# ESP32_Module.net
KiCad netlist of a schematic drawn in EAGLE
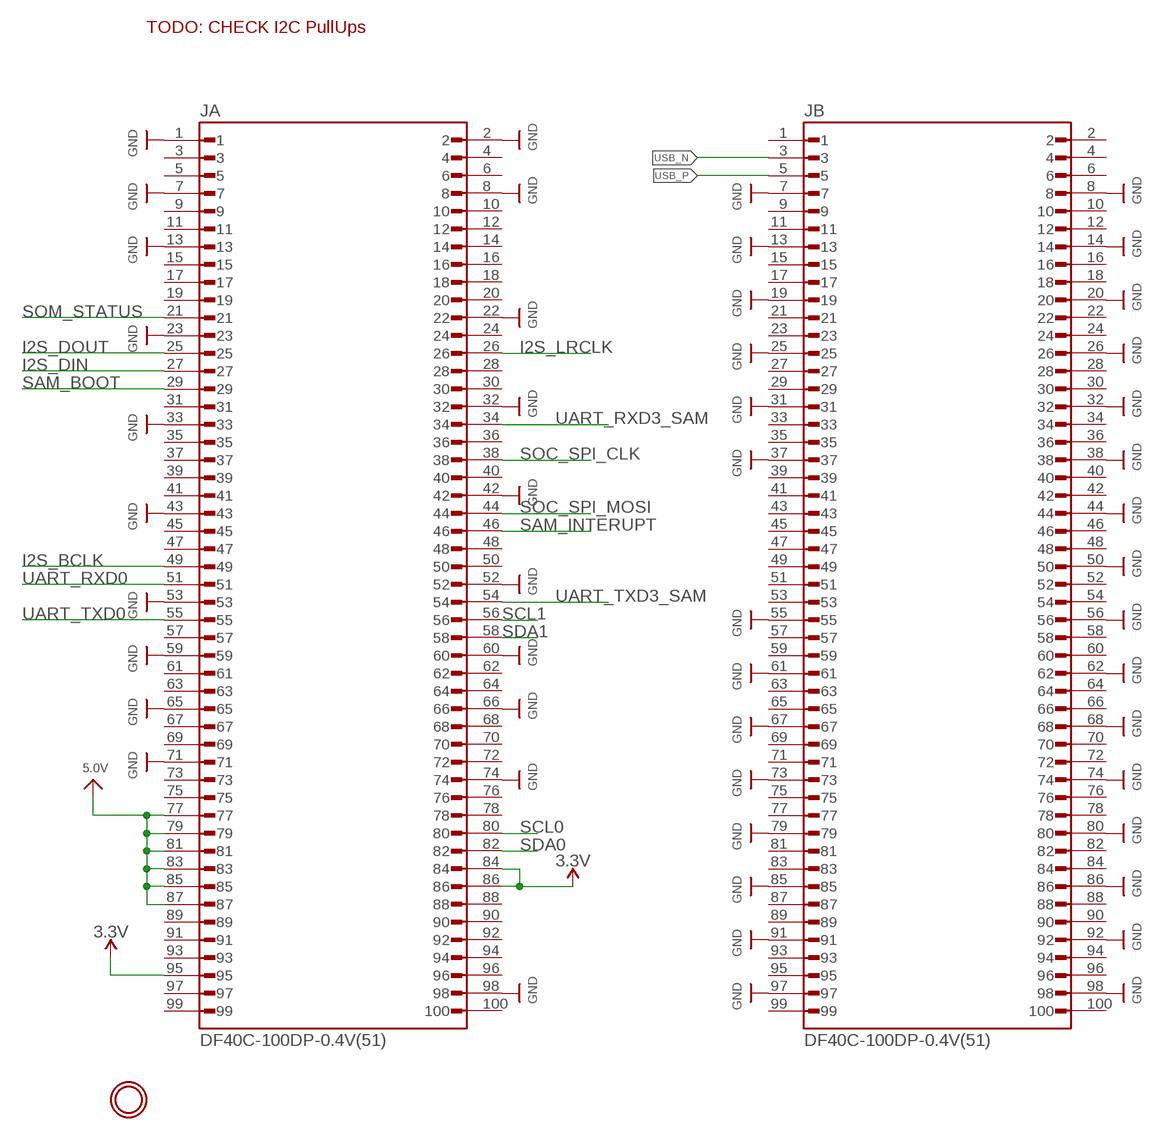
[diagram p0: schematic, sheet 1, part 1 of 3]
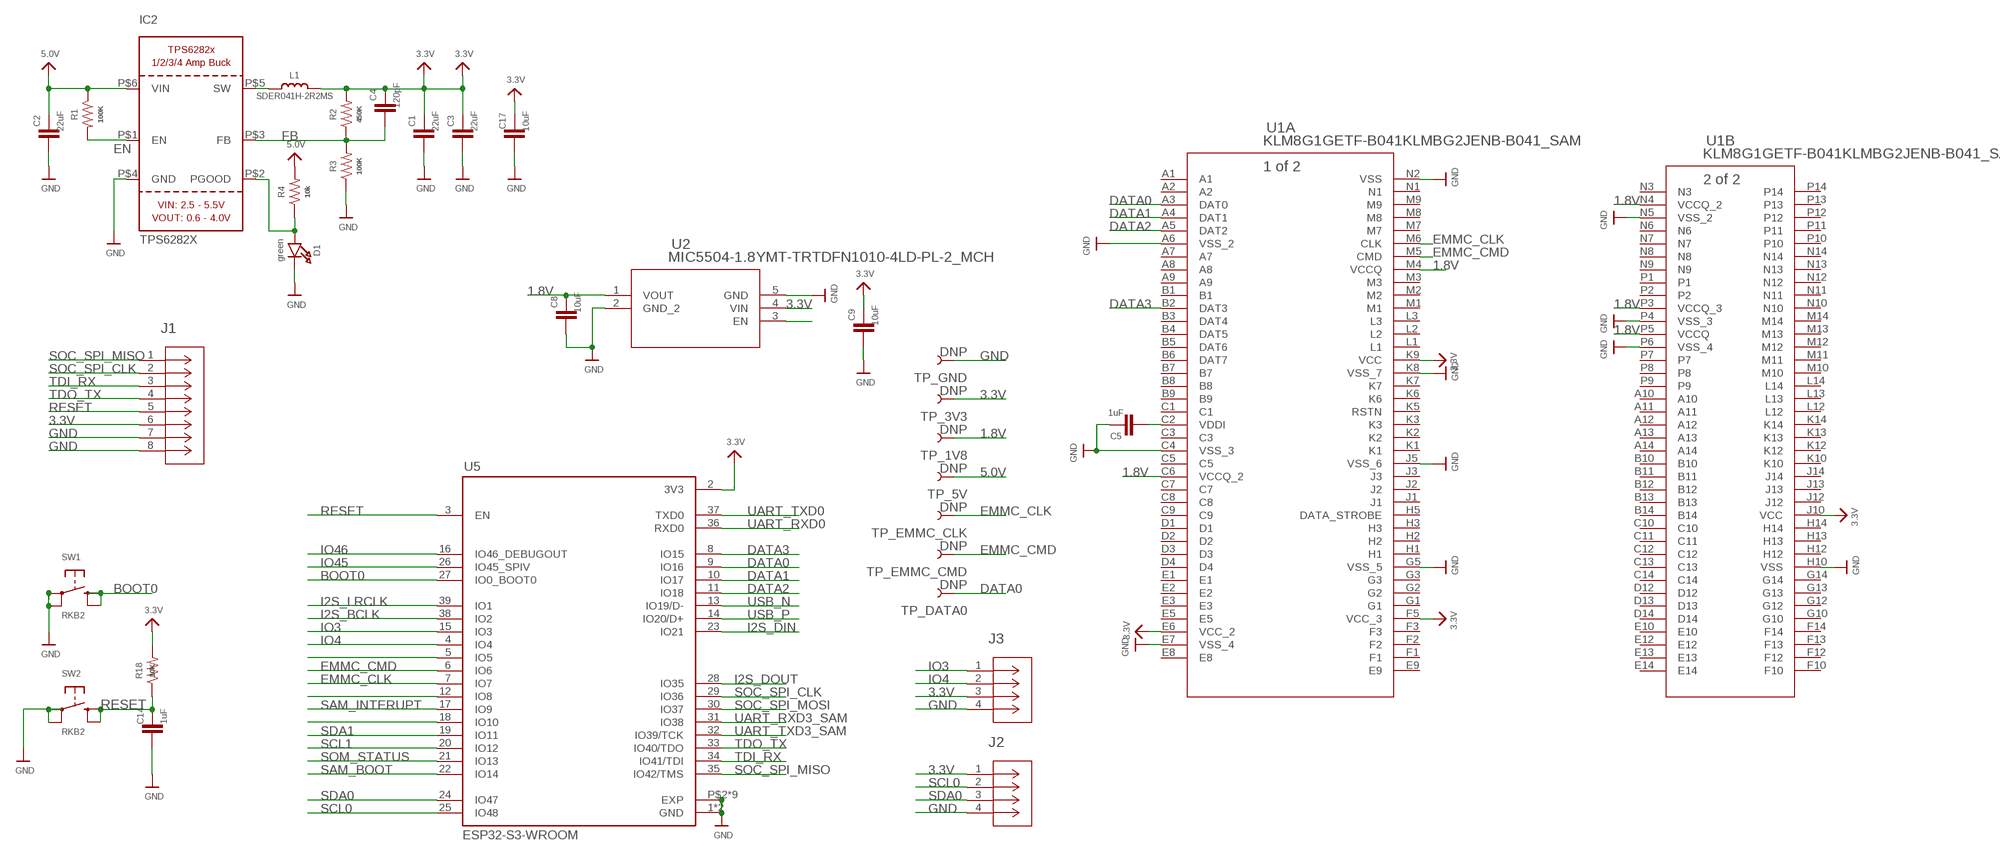
[diagram p1: schematic, sheet 1, part 2 of 3]
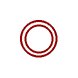
[diagram p2: schematic, sheet 1, part 3 of 3]

(export (version "E")
  (design (tool "Eeschema 10.0.6"))
  (components
    (comp (ref "C1")
      (value "22uF")
      (footprint "eagle-import:CAPC1005X60")
      (libsource (lib "eagle-import") (part "CCHIP-0402(1005-METRIC)_"))
    )
    (comp (ref "C2")
      (value "22uF")
      (footprint "eagle-import:CAPC1608X85")
      (libsource (lib "eagle-import") (part "CCHIP-0603(1608-METRIC)_"))
    )
    (comp (ref "C3")
      (value "22uF")
      (footprint "eagle-import:CAPC1005X60")
      (libsource (lib "eagle-import") (part "CCHIP-0402(1005-METRIC)_"))
    )
    (comp (ref "C4")
      (value "120pF")
      (footprint "eagle-import:CAPC1005X60")
      (libsource (lib "eagle-import") (part "CCHIP-0402(1005-METRIC)_"))
    )
    (comp (ref "C5")
      (value "1uF")
      (footprint "eagle-import:CAPC1005X60")
      (libsource (lib "eagle-import") (part "CCHIP-0402(1005-METRIC)_"))
    )
    (comp (ref "C8")
      (value "10uF")
      (footprint "eagle-import:CAPC1005X60")
      (libsource (lib "eagle-import") (part "CCHIP-0402(1005-METRIC)_"))
    )
    (comp (ref "C9")
      (value "10uF")
      (footprint "eagle-import:CAPC1005X60")
      (libsource (lib "eagle-import") (part "CCHIP-0402(1005-METRIC)_"))
    )
    (comp (ref "C14")
      (value "1uF")
      (footprint "eagle-import:CAPC1005X60")
      (libsource (lib "eagle-import") (part "CCHIP-0402(1005-METRIC)_"))
    )
    (comp (ref "C17")
      (value "10uF")
      (footprint "eagle-import:CAPC1005X60")
      (libsource (lib "eagle-import") (part "CCHIP-0402(1005-METRIC)_"))
    )
    (comp (ref "D1")
      (value "green")
      (footprint "eagle-import:CHIPLED_0603_NOOUTLINE")
      (libsource (lib "eagle-import") (part "LED0603_NOOUTLINE"))
    )
    (comp (ref "IC2")
      (value "TPS6282X")
      (footprint "eagle-import:VSON_6")
      (libsource (lib "eagle-import") (part "TPS6282X"))
    )
    (comp (ref "J1")
      (value "SM08B-SRSS-TB(LF)(SN)CONN_SM08B-SRSS-TB(LF)(SN)_JST")
      (footprint "eagle-import:CONN_SM08B-SRSS-TB(LF)(SN)_JST")
      (fields
        (field (name "MANUFACTURER_PART_NUMBER") "SM08B-SRSS-TB(LF)(SN)")
        (field (name "COPYRIGHT") "Copyright (C) 2024 Ultra Librarian. All rights reserved.")
      )
      (libsource (lib "eagle-import") (part "SM08B-SRSS-TB(LF)(SN)CONN_SM08B-SRSS-TB(LF)(SN)_JST"))
    )
    (comp (ref "J2")
      (value "SM04B-SRSS-TBCONN_SM04B-SRSS-TB_JST")
      (footprint "eagle-import:CONN_SM04B-SRSS-TB_JST")
      (fields
        (field (name "MANUFACTURER_PART_NUMBER") "SM04B-SRSS-TB")
        (field (name "COPYRIGHT") "Copyright (C) 2024 Ultra Librarian. All rights reserved.")
      )
      (libsource (lib "eagle-import") (part "SM04B-SRSS-TBCONN_SM04B-SRSS-TB_JST"))
    )
    (comp (ref "J3")
      (value "SM04B-SRSS-TBCONN_SM04B-SRSS-TB_JST")
      (footprint "eagle-import:CONN_SM04B-SRSS-TB_JST")
      (fields
        (field (name "MANUFACTURER_PART_NUMBER") "SM04B-SRSS-TB")
        (field (name "COPYRIGHT") "Copyright (C) 2024 Ultra Librarian. All rights reserved.")
      )
      (libsource (lib "eagle-import") (part "SM04B-SRSS-TBCONN_SM04B-SRSS-TB_JST"))
    )
    (comp (ref "JA")
      (value "DF40C-100DP-0.4V(51)")
      (footprint "eagle-import:HIROSE_DF40C-100DP-0.4V(51)")
      (fields (field (name "MANUFACTURER") "Hirose"))
      (libsource (lib "eagle-import") (part "DF40C-100DP-0.4V(51)"))
    )
    (comp (ref "JB")
      (value "DF40C-100DP-0.4V(51)")
      (footprint "eagle-import:HIROSE_DF40C-100DP-0.4V(51)")
      (fields (field (name "MANUFACTURER") "Hirose"))
      (libsource (lib "eagle-import") (part "DF40C-100DP-0.4V(51)"))
    )
    (comp (ref "L1")
      (value "SDER041H-2R2MS")
      (footprint "eagle-import:INDUCTOR_4X4MM_SRP0415")
      (libsource (lib "eagle-import") (part "INDUCTOR_SRP0415"))
    )
    (comp (ref "R1")
      (value "100K")
      (footprint "eagle-import:RESC1005X40")
      (libsource (lib "eagle-import") (part "R-USCHIP-0402(1005-METRIC)_"))
    )
    (comp (ref "R2")
      (value "450K")
      (footprint "eagle-import:RESC1005X40")
      (libsource (lib "eagle-import") (part "R-USCHIP-0402(1005-METRIC)_"))
    )
    (comp (ref "R3")
      (value "100K")
      (footprint "eagle-import:RESC1005X40")
      (libsource (lib "eagle-import") (part "R-USCHIP-0402(1005-METRIC)_"))
    )
    (comp (ref "R4")
      (value "10k")
      (footprint "eagle-import:RESC1005X40")
      (libsource (lib "eagle-import") (part "R-USCHIP-0402(1005-METRIC)_"))
    )
    (comp (ref "R18")
      (value "10K")
      (footprint "eagle-import:RESC1005X40")
      (libsource (lib "eagle-import") (part "R-USCHIP-0402(1005-METRIC)_"))
    )
    (comp (ref "SW1")
      (value "RKB2")
      (footprint "eagle-import:BTN_RKB2_4.6X2.8")
      (libsource (lib "eagle-import") (part "SWITCH_TACT_SMT_RKB2"))
    )
    (comp (ref "SW2")
      (value "RKB2")
      (footprint "eagle-import:BTN_RKB2_4.6X2.8")
      (libsource (lib "eagle-import") (part "SWITCH_TACT_SMT_RKB2"))
    )
    (comp (ref "TP_1V8")
      (value "DNP")
      (footprint "eagle-import:PAD.03X.03")
      (libsource (lib "eagle-import") (part "TEST-POINT3"))
    )
    (comp (ref "TP_3V3")
      (value "DNP")
      (footprint "eagle-import:PAD.03X.03")
      (libsource (lib "eagle-import") (part "TEST-POINT3"))
    )
    (comp (ref "TP_5V")
      (value "DNP")
      (footprint "eagle-import:PAD.03X.03")
      (libsource (lib "eagle-import") (part "TEST-POINT3"))
    )
    (comp (ref "TP_DATA0")
      (value "DNP")
      (footprint "eagle-import:PAD.03X.03")
      (libsource (lib "eagle-import") (part "TEST-POINT3"))
    )
    (comp (ref "TP_EMMC_CLK")
      (value "DNP")
      (footprint "eagle-import:PAD.03X.03")
      (libsource (lib "eagle-import") (part "TEST-POINT3"))
    )
    (comp (ref "TP_EMMC_CMD")
      (value "DNP")
      (footprint "eagle-import:PAD.03X.03")
      (libsource (lib "eagle-import") (part "TEST-POINT3"))
    )
    (comp (ref "TP_GND")
      (value "DNP")
      (footprint "eagle-import:PAD.03X.03")
      (libsource (lib "eagle-import") (part "TEST-POINT3"))
    )
    (comp (ref "U$2")
      (value "MOUNTINGHOLE2.5")
      (footprint "eagle-import:MOUNTINGHOLE_2.5_PLATED")
      (libsource (lib "eagle-import") (part "MOUNTINGHOLE2.5"))
    )
    (comp (ref "U$120")
      (value "MOUNTINGHOLE2.5")
      (footprint "eagle-import:MOUNTINGHOLE_2.5_PLATED")
      (libsource (lib "eagle-import") (part "MOUNTINGHOLE2.5"))
    )
    (comp (ref "U1")
      (value "KLM8G1GETF-B041KLMBG2JENB-B041_SAM")
      (footprint "eagle-import:KLMBG2JENB-B041_SAM")
      (fields
        (field (name "MANUFACTURER_PART_NUMBER") "KLM8G1GETF-B041")
        (field (name "COPYRIGHT") "Copyright (C) 2024 Ultra Librarian. All rights reserved.")
      )
      (libsource (lib "eagle-import") (part "KLM8G1GETF-B041KLMBG2JENB-B041_SAM"))
    )
    (comp (ref "U2")
      (value "MIC5504-1.8YMT-TRTDFN1010-4LD-PL-2_MCH")
      (footprint "eagle-import:TDFN1010-4LD-PL-2_MCH")
      (fields
        (field (name "MANUFACTURER_PART_NUMBER") "MIC5504-1.8YMT-TR")
        (field (name "COPYRIGHT") "Copyright (C) 2024 Ultra Librarian. All rights reserved.")
      )
      (libsource (lib "eagle-import") (part "MIC5504-1.8YMT-TRTDFN1010-4LD-PL-2_MCH"))
    )
    (comp (ref "U5")
      (value "ESP32-S3-WROOM")
      (footprint "eagle-import:S3-WROOM32")
      (libsource (lib "eagle-import") (part "ESP32-S3-WROOM"))
    )
  )
  (nets
    (net (code "1") (name "/1.8V") (class "Default")
      (node (ref "C8") (pin "1") (pinfunction "1_1") (pintype "passive"))
      (node (ref "TP_1V8") (pin "P$1") (pinfunction "1_P$1") (pintype "bidirectional"))
      (node (ref "U1") (pin "C6") (pinfunction "VCCQ_2_C6") (pintype "power_in"))
      (node (ref "U1") (pin "M4") (pinfunction "VCCQ_M4") (pintype "power_in"))
      (node (ref "U1") (pin "N4") (pinfunction "VCCQ_2_N4") (pintype "power_in"))
      (node (ref "U1") (pin "P3") (pinfunction "VCCQ_3_P3") (pintype "power_in"))
      (node (ref "U1") (pin "P5") (pinfunction "VCCQ_P5") (pintype "power_in"))
      (node (ref "U2") (pin "1") (pinfunction "VOUT_1") (pintype "output"))
    )
    (net (code "2") (name "/BOOT0") (class "Default")
      (node (ref "SW1") (pin "B") (pinfunction "S_B") (pintype "passive"))
      (node (ref "SW1") (pin "B'") (pinfunction "S1_B'") (pintype "passive"))
      (node (ref "U5") (pin "27") (pinfunction "IO0_BOOT0_27") (pintype "bidirectional"))
    )
    (net (code "3") (name "/DATA0") (class "Default")
      (node (ref "TP_DATA0") (pin "P$1") (pinfunction "1_P$1") (pintype "bidirectional"))
      (node (ref "U1") (pin "A3") (pinfunction "DAT0_A3") (pintype "bidirectional"))
      (node (ref "U5") (pin "9") (pinfunction "IO16_9") (pintype "bidirectional"))
    )
    (net (code "4") (name "/DATA1") (class "Default")
      (node (ref "U1") (pin "A4") (pinfunction "DAT1_A4") (pintype "bidirectional"))
      (node (ref "U5") (pin "10") (pinfunction "IO17_10") (pintype "bidirectional"))
    )
    (net (code "5") (name "/DATA2") (class "Default")
      (node (ref "U1") (pin "A5") (pinfunction "DAT2_A5") (pintype "bidirectional"))
      (node (ref "U5") (pin "11") (pinfunction "IO18_11") (pintype "bidirectional"))
    )
    (net (code "6") (name "/DATA3") (class "Default")
      (node (ref "U1") (pin "B2") (pinfunction "DAT3_B2") (pintype "bidirectional"))
      (node (ref "U5") (pin "8") (pinfunction "IO15_8") (pintype "bidirectional"))
    )
    (net (code "7") (name "/EMMC_CLK") (class "Default")
      (node (ref "TP_EMMC_CLK") (pin "P$1") (pinfunction "1_P$1") (pintype "bidirectional"))
      (node (ref "U1") (pin "M6") (pinfunction "CLK_M6") (pintype "passive"))
      (node (ref "U5") (pin "7") (pinfunction "IO7_7") (pintype "bidirectional"))
    )
    (net (code "8") (name "/EMMC_CMD") (class "Default")
      (node (ref "TP_EMMC_CMD") (pin "P$1") (pinfunction "1_P$1") (pintype "bidirectional"))
      (node (ref "U1") (pin "M5") (pinfunction "CMD_M5") (pintype "passive"))
      (node (ref "U5") (pin "6") (pinfunction "IO6_6") (pintype "bidirectional"))
    )
    (net (code "9") (name "/EN") (class "Default")
      (node (ref "IC2") (pin "P$1") (pinfunction "EN_P$1") (pintype "input"))
      (node (ref "R1") (pin "2") (pinfunction "2_2") (pintype "passive"))
    )
    (net (code "10") (name "/FB") (class "Default")
      (node (ref "C4") (pin "2") (pinfunction "2_2") (pintype "passive"))
      (node (ref "IC2") (pin "P$3") (pinfunction "FB_P$3") (pintype "input"))
      (node (ref "R2") (pin "1") (pinfunction "1_1") (pintype "passive"))
      (node (ref "R3") (pin "2") (pinfunction "2_2") (pintype "passive"))
    )
    (net (code "11") (name "/I2S_BCLK") (class "Default")
      (node (ref "JA") (pin "49") (pinfunction "49_49") (pintype "passive"))
      (node (ref "U5") (pin "38") (pinfunction "IO2_38") (pintype "bidirectional"))
    )
    (net (code "12") (name "/I2S_DIN") (class "Default")
      (node (ref "JA") (pin "27") (pinfunction "27_27") (pintype "passive"))
      (node (ref "U5") (pin "23") (pinfunction "IO21_23") (pintype "bidirectional"))
    )
    (net (code "13") (name "/I2S_DOUT") (class "Default")
      (node (ref "JA") (pin "25") (pinfunction "25_25") (pintype "passive"))
      (node (ref "U5") (pin "28") (pinfunction "IO35_28") (pintype "input"))
    )
    (net (code "14") (name "/I2S_LRCLK") (class "Default")
      (node (ref "JA") (pin "26") (pinfunction "26_26") (pintype "passive"))
      (node (ref "U5") (pin "39") (pinfunction "IO1_39") (pintype "bidirectional"))
    )
    (net (code "15") (name "/IO3") (class "Default")
      (node (ref "J3") (pin "1") (pinfunction "1_1") (pintype "passive"))
      (node (ref "U5") (pin "15") (pinfunction "IO3_15") (pintype "bidirectional"))
    )
    (net (code "16") (name "/IO4") (class "Default")
      (node (ref "J3") (pin "2") (pinfunction "2_2") (pintype "passive"))
      (node (ref "U5") (pin "4") (pinfunction "IO4_4") (pintype "bidirectional"))
    )
    (net (code "17") (name "/IO45") (class "Default")
      (node (ref "U5") (pin "26") (pinfunction "IO45_SPIV_26") (pintype "bidirectional"))
    )
    (net (code "18") (name "/IO46") (class "Default")
      (node (ref "U5") (pin "16") (pinfunction "IO46_DEBUGOUT_16") (pintype "input"))
    )
    (net (code "19") (name "/RESET") (class "Default")
      (node (ref "C14") (pin "1") (pinfunction "1_1") (pintype "passive"))
      (node (ref "J1") (pin "5") (pinfunction "5_5") (pintype "passive"))
      (node (ref "R18") (pin "1") (pinfunction "1_1") (pintype "passive"))
      (node (ref "SW2") (pin "B") (pinfunction "S_B") (pintype "passive"))
      (node (ref "SW2") (pin "B'") (pinfunction "S1_B'") (pintype "passive"))
      (node (ref "U5") (pin "3") (pinfunction "EN_3") (pintype "input"))
    )
    (net (code "20") (name "/SAM_BOOT") (class "Default")
      (node (ref "JA") (pin "29") (pinfunction "29_29") (pintype "passive"))
      (node (ref "U5") (pin "22") (pinfunction "IO14_22") (pintype "bidirectional"))
    )
    (net (code "21") (name "/SAM_INTERUPT") (class "Default")
      (node (ref "JA") (pin "46") (pinfunction "46_46") (pintype "passive"))
      (node (ref "U5") (pin "17") (pinfunction "IO9_17") (pintype "bidirectional"))
    )
    (net (code "22") (name "/SCL0") (class "Default")
      (node (ref "J2") (pin "2") (pinfunction "2_2") (pintype "passive"))
      (node (ref "JA") (pin "80") (pinfunction "80_80") (pintype "passive"))
      (node (ref "U5") (pin "25") (pinfunction "IO48_25") (pintype "input"))
    )
    (net (code "23") (name "/SCL1") (class "Default")
      (node (ref "JA") (pin "56") (pinfunction "56_56") (pintype "passive"))
      (node (ref "U5") (pin "20") (pinfunction "IO12_20") (pintype "bidirectional"))
    )
    (net (code "24") (name "/SDA0") (class "Default")
      (node (ref "J2") (pin "3") (pinfunction "3_3") (pintype "passive"))
      (node (ref "JA") (pin "82") (pinfunction "82_82") (pintype "passive"))
      (node (ref "U5") (pin "24") (pinfunction "IO47_24") (pintype "bidirectional"))
    )
    (net (code "25") (name "/SDA1") (class "Default")
      (node (ref "JA") (pin "58") (pinfunction "58_58") (pintype "passive"))
      (node (ref "U5") (pin "19") (pinfunction "IO11_19") (pintype "bidirectional"))
    )
    (net (code "26") (name "/SOC_SPI_CLK") (class "Default")
      (node (ref "J1") (pin "2") (pinfunction "2_2") (pintype "passive"))
      (node (ref "JA") (pin "38") (pinfunction "38_38") (pintype "passive"))
      (node (ref "U5") (pin "29") (pinfunction "IO36_29") (pintype "bidirectional"))
    )
    (net (code "27") (name "/SOC_SPI_MISO") (class "Default")
      (node (ref "J1") (pin "1") (pinfunction "1_1") (pintype "passive"))
      (node (ref "U5") (pin "35") (pinfunction "IO42/TMS_35") (pintype "bidirectional"))
    )
    (net (code "28") (name "/SOC_SPI_MOSI") (class "Default")
      (node (ref "JA") (pin "44") (pinfunction "44_44") (pintype "passive"))
      (node (ref "U5") (pin "30") (pinfunction "IO37_30") (pintype "bidirectional"))
    )
    (net (code "29") (name "/SOM_STATUS") (class "Default")
      (node (ref "JA") (pin "21") (pinfunction "21_21") (pintype "passive"))
      (node (ref "U5") (pin "21") (pinfunction "IO13_21") (pintype "bidirectional"))
    )
    (net (code "30") (name "/TDI_RX") (class "Default")
      (node (ref "J1") (pin "3") (pinfunction "3_3") (pintype "passive"))
      (node (ref "U5") (pin "34") (pinfunction "IO41/TDI_34") (pintype "bidirectional"))
    )
    (net (code "31") (name "/TDO_TX") (class "Default")
      (node (ref "J1") (pin "4") (pinfunction "4_4") (pintype "passive"))
      (node (ref "U5") (pin "33") (pinfunction "IO40/TDO_33") (pintype "bidirectional"))
    )
    (net (code "32") (name "/UART_RXD0") (class "Default")
      (node (ref "JA") (pin "51") (pinfunction "51_51") (pintype "passive"))
      (node (ref "U5") (pin "36") (pinfunction "RXD0_36") (pintype "bidirectional"))
    )
    (net (code "33") (name "/UART_RXD3_SAM") (class "Default")
      (node (ref "JA") (pin "34") (pinfunction "34_34") (pintype "passive"))
      (node (ref "U5") (pin "31") (pinfunction "IO38_31") (pintype "bidirectional"))
    )
    (net (code "34") (name "/UART_TXD0") (class "Default")
      (node (ref "JA") (pin "55") (pinfunction "55_55") (pintype "passive"))
      (node (ref "U5") (pin "37") (pinfunction "TXD0_37") (pintype "bidirectional"))
    )
    (net (code "35") (name "/UART_TXD3_SAM") (class "Default")
      (node (ref "JA") (pin "54") (pinfunction "54_54") (pintype "passive"))
      (node (ref "U5") (pin "32") (pinfunction "IO39/TCK_32") (pintype "bidirectional"))
    )
    (net (code "36") (name "3.3V") (class "Default")
      (node (ref "C1") (pin "1") (pinfunction "1_1") (pintype "passive"))
      (node (ref "C17") (pin "1") (pinfunction "1_1") (pintype "passive"))
      (node (ref "C3") (pin "1") (pinfunction "1_1") (pintype "passive"))
      (node (ref "C4") (pin "1") (pinfunction "1_1") (pintype "passive"))
      (node (ref "C9") (pin "1") (pinfunction "1_1") (pintype "passive"))
      (node (ref "J1") (pin "6") (pinfunction "6_6") (pintype "passive"))
      (node (ref "J2") (pin "1") (pinfunction "1_1") (pintype "passive"))
      (node (ref "J3") (pin "3") (pinfunction "3_3") (pintype "passive"))
      (node (ref "JA") (pin "84") (pinfunction "84_84") (pintype "passive"))
      (node (ref "JA") (pin "86") (pinfunction "86_86") (pintype "passive"))
      (node (ref "JA") (pin "95") (pinfunction "95_95") (pintype "passive"))
      (node (ref "L1") (pin "P$2") (pinfunction "2_P$2") (pintype "passive"))
      (node (ref "R18") (pin "2") (pinfunction "2_2") (pintype "passive"))
      (node (ref "R2") (pin "2") (pinfunction "2_2") (pintype "passive"))
      (node (ref "TP_3V3") (pin "P$1") (pinfunction "1_P$1") (pintype "bidirectional"))
      (node (ref "U1") (pin "E6") (pinfunction "VCC_2_E6") (pintype "power_in"))
      (node (ref "U1") (pin "F5") (pinfunction "VCC_3_F5") (pintype "power_in"))
      (node (ref "U1") (pin "J10") (pinfunction "VCC_J10") (pintype "power_in"))
      (node (ref "U1") (pin "K9") (pinfunction "VCC_K9") (pintype "power_in"))
      (node (ref "U2") (pin "4") (pinfunction "VIN_4") (pintype "power_in"))
      (node (ref "U5") (pin "2") (pinfunction "3V3_2") (pintype "power_in"))
    )
    (net (code "37") (name "5.0V") (class "Default")
      (node (ref "C2") (pin "1") (pinfunction "1_1") (pintype "passive"))
      (node (ref "IC2") (pin "P$6") (pinfunction "VIN_P$6") (pintype "power_in"))
      (node (ref "JA") (pin "77") (pinfunction "77_77") (pintype "passive"))
      (node (ref "JA") (pin "79") (pinfunction "79_79") (pintype "passive"))
      (node (ref "JA") (pin "81") (pinfunction "81_81") (pintype "passive"))
      (node (ref "JA") (pin "83") (pinfunction "83_83") (pintype "passive"))
      (node (ref "JA") (pin "85") (pinfunction "85_85") (pintype "passive"))
      (node (ref "JA") (pin "87") (pinfunction "87_87") (pintype "passive"))
      (node (ref "R1") (pin "1") (pinfunction "1_1") (pintype "passive"))
      (node (ref "R4") (pin "2") (pinfunction "2_2") (pintype "passive"))
      (node (ref "TP_5V") (pin "P$1") (pinfunction "1_P$1") (pintype "bidirectional"))
    )
    (net (code "38") (name "GND") (class "Default")
      (node (ref "C1") (pin "2") (pinfunction "2_2") (pintype "passive"))
      (node (ref "C14") (pin "2") (pinfunction "2_2") (pintype "passive"))
      (node (ref "C17") (pin "2") (pinfunction "2_2") (pintype "passive"))
      (node (ref "C2") (pin "2") (pinfunction "2_2") (pintype "passive"))
      (node (ref "C3") (pin "2") (pinfunction "2_2") (pintype "passive"))
      (node (ref "C5") (pin "1") (pinfunction "1_1") (pintype "passive"))
      (node (ref "C8") (pin "2") (pinfunction "2_2") (pintype "passive"))
      (node (ref "C9") (pin "2") (pinfunction "2_2") (pintype "passive"))
      (node (ref "D1") (pin "C") (pinfunction "C_C") (pintype "passive"))
      (node (ref "IC2") (pin "P$4") (pinfunction "GND_P$4") (pintype "power_in"))
      (node (ref "J1") (pin "7") (pinfunction "7_7") (pintype "passive"))
      (node (ref "J1") (pin "8") (pinfunction "8_8") (pintype "passive"))
      (node (ref "J2") (pin "4") (pinfunction "4_4") (pintype "passive"))
      (node (ref "J3") (pin "4") (pinfunction "4_4") (pintype "passive"))
      (node (ref "JA") (pin "1") (pinfunction "1_1") (pintype "passive"))
      (node (ref "JA") (pin "13") (pinfunction "13_13") (pintype "passive"))
      (node (ref "JA") (pin "2") (pinfunction "2_2") (pintype "passive"))
      (node (ref "JA") (pin "22") (pinfunction "22_22") (pintype "passive"))
      (node (ref "JA") (pin "23") (pinfunction "23_23") (pintype "passive"))
      (node (ref "JA") (pin "32") (pinfunction "32_32") (pintype "passive"))
      (node (ref "JA") (pin "33") (pinfunction "33_33") (pintype "passive"))
      (node (ref "JA") (pin "42") (pinfunction "42_42") (pintype "passive"))
      (node (ref "JA") (pin "43") (pinfunction "43_43") (pintype "passive"))
      (node (ref "JA") (pin "52") (pinfunction "52_52") (pintype "passive"))
      (node (ref "JA") (pin "53") (pinfunction "53_53") (pintype "passive"))
      (node (ref "JA") (pin "59") (pinfunction "59_59") (pintype "passive"))
      (node (ref "JA") (pin "60") (pinfunction "60_60") (pintype "passive"))
      (node (ref "JA") (pin "65") (pinfunction "65_65") (pintype "passive"))
      (node (ref "JA") (pin "66") (pinfunction "66_66") (pintype "passive"))
      (node (ref "JA") (pin "7") (pinfunction "7_7") (pintype "passive"))
      (node (ref "JA") (pin "71") (pinfunction "71_71") (pintype "passive"))
      (node (ref "JA") (pin "74") (pinfunction "74_74") (pintype "passive"))
      (node (ref "JA") (pin "8") (pinfunction "8_8") (pintype "passive"))
      (node (ref "JA") (pin "98") (pinfunction "98_98") (pintype "passive"))
      (node (ref "JB") (pin "13") (pinfunction "13_13") (pintype "passive"))
      (node (ref "JB") (pin "14") (pinfunction "14_14") (pintype "passive"))
      (node (ref "JB") (pin "19") (pinfunction "19_19") (pintype "passive"))
      (node (ref "JB") (pin "20") (pinfunction "20_20") (pintype "passive"))
      (node (ref "JB") (pin "25") (pinfunction "25_25") (pintype "passive"))
      (node (ref "JB") (pin "26") (pinfunction "26_26") (pintype "passive"))
      (node (ref "JB") (pin "31") (pinfunction "31_31") (pintype "passive"))
      (node (ref "JB") (pin "32") (pinfunction "32_32") (pintype "passive"))
      (node (ref "JB") (pin "37") (pinfunction "37_37") (pintype "passive"))
      (node (ref "JB") (pin "38") (pinfunction "38_38") (pintype "passive"))
      (node (ref "JB") (pin "44") (pinfunction "44_44") (pintype "passive"))
      (node (ref "JB") (pin "50") (pinfunction "50_50") (pintype "passive"))
      (node (ref "JB") (pin "55") (pinfunction "55_55") (pintype "passive"))
      (node (ref "JB") (pin "56") (pinfunction "56_56") (pintype "passive"))
      (node (ref "JB") (pin "61") (pinfunction "61_61") (pintype "passive"))
      (node (ref "JB") (pin "62") (pinfunction "62_62") (pintype "passive"))
      (node (ref "JB") (pin "67") (pinfunction "67_67") (pintype "passive"))
      (node (ref "JB") (pin "68") (pinfunction "68_68") (pintype "passive"))
      (node (ref "JB") (pin "7") (pinfunction "7_7") (pintype "passive"))
      (node (ref "JB") (pin "73") (pinfunction "73_73") (pintype "passive"))
      (node (ref "JB") (pin "74") (pinfunction "74_74") (pintype "passive"))
      (node (ref "JB") (pin "79") (pinfunction "79_79") (pintype "passive"))
      (node (ref "JB") (pin "8") (pinfunction "8_8") (pintype "passive"))
      (node (ref "JB") (pin "80") (pinfunction "80_80") (pintype "passive"))
      (node (ref "JB") (pin "85") (pinfunction "85_85") (pintype "passive"))
      (node (ref "JB") (pin "86") (pinfunction "86_86") (pintype "passive"))
      (node (ref "JB") (pin "91") (pinfunction "91_91") (pintype "passive"))
      (node (ref "JB") (pin "92") (pinfunction "92_92") (pintype "passive"))
      (node (ref "JB") (pin "97") (pinfunction "97_97") (pintype "passive"))
      (node (ref "JB") (pin "98") (pinfunction "98_98") (pintype "passive"))
      (node (ref "R3") (pin "1") (pinfunction "1_1") (pintype "passive"))
      (node (ref "SW1") (pin "A") (pinfunction "P_A") (pintype "passive"))
      (node (ref "SW1") (pin "A'") (pinfunction "P1_A'") (pintype "passive"))
      (node (ref "SW2") (pin "A") (pinfunction "P_A") (pintype "passive"))
      (node (ref "SW2") (pin "A'") (pinfunction "P1_A'") (pintype "passive"))
      (node (ref "TP_GND") (pin "P$1") (pinfunction "1_P$1") (pintype "bidirectional"))
      (node (ref "U1") (pin "A6") (pinfunction "VSS_2_A6") (pintype "passive"))
      (node (ref "U1") (pin "C4") (pinfunction "VSS_3_C4") (pintype "passive"))
      (node (ref "U1") (pin "E7") (pinfunction "VSS_4_E7") (pintype "passive"))
      (node (ref "U1") (pin "G5") (pinfunction "VSS_5_G5") (pintype "passive"))
      (node (ref "U1") (pin "H10") (pinfunction "VSS_H10") (pintype "passive"))
      (node (ref "U1") (pin "J5") (pinfunction "VSS_6_J5") (pintype "passive"))
      (node (ref "U1") (pin "K8") (pinfunction "VSS_7_K8") (pintype "passive"))
      (node (ref "U1") (pin "N2") (pinfunction "VSS_N2") (pintype "passive"))
      (node (ref "U1") (pin "N5") (pinfunction "VSS_2_N5") (pintype "passive"))
      (node (ref "U1") (pin "P4") (pinfunction "VSS_3_P4") (pintype "passive"))
      (node (ref "U1") (pin "P6") (pinfunction "VSS_4_P6") (pintype "passive"))
      (node (ref "U2") (pin "2") (pinfunction "GND_2_2") (pintype "passive"))
      (node (ref "U2") (pin "5") (pinfunction "GND_5") (pintype "passive"))
      (node (ref "U5") (pin "1") (pinfunction "GND_1") (pintype "power_in"))
      (node (ref "U5") (pin "40") (pinfunction "GND_40") (pintype "power_in"))
      (node (ref "U5") (pin "P$10") (pinfunction "EXP_P$10") (pintype "power_in"))
      (node (ref "U5") (pin "P$2") (pinfunction "EXP_P$2") (pintype "power_in"))
      (node (ref "U5") (pin "P$3") (pinfunction "EXP_P$3") (pintype "power_in"))
      (node (ref "U5") (pin "P$4") (pinfunction "EXP_P$4") (pintype "power_in"))
      (node (ref "U5") (pin "P$5") (pinfunction "EXP_P$5") (pintype "power_in"))
      (node (ref "U5") (pin "P$6") (pinfunction "EXP_P$6") (pintype "power_in"))
      (node (ref "U5") (pin "P$7") (pinfunction "EXP_P$7") (pintype "power_in"))
      (node (ref "U5") (pin "P$8") (pinfunction "EXP_P$8") (pintype "power_in"))
      (node (ref "U5") (pin "P$9") (pinfunction "EXP_P$9") (pintype "power_in"))
    )
    (net (code "39") (name "Net-(IC2-PGOOD)") (class "Default")
      (node (ref "D1") (pin "A") (pinfunction "A_A") (pintype "passive"))
      (node (ref "IC2") (pin "P$2") (pinfunction "PGOOD_P$2") (pintype "output"))
      (node (ref "R4") (pin "1") (pinfunction "1_1") (pintype "passive"))
    )
    (net (code "40") (name "Net-(IC2-SW)") (class "Default")
      (node (ref "IC2") (pin "P$5") (pinfunction "SW_P$5") (pintype "power_in"))
      (node (ref "L1") (pin "P$1") (pinfunction "1_P$1") (pintype "passive"))
    )
    (net (code "41") (name "Net-(U1A-VDDI)") (class "Default")
      (node (ref "C5") (pin "2") (pinfunction "2_2") (pintype "passive"))
      (node (ref "U1") (pin "C2") (pinfunction "VDDI_C2") (pintype "power_in"))
    )
    (net (code "42") (name "USB_N") (class "Default")
      (node (ref "JB") (pin "3") (pinfunction "3_3") (pintype "passive"))
      (node (ref "U5") (pin "13") (pinfunction "IO19/D-_13") (pintype "bidirectional"))
    )
    (net (code "43") (name "USB_P") (class "Default")
      (node (ref "JB") (pin "5") (pinfunction "5_5") (pintype "passive"))
      (node (ref "U5") (pin "14") (pinfunction "IO20/D+_14") (pintype "bidirectional"))
    )
    (net (code "44") (name "unconnected-(JA-Pad3)") (class "Default")
      (node (ref "JA") (pin "3") (pinfunction "3_3") (pintype "passive"))
    )
    (net (code "45") (name "unconnected-(JA-Pad4)") (class "Default")
      (node (ref "JA") (pin "4") (pinfunction "4_4") (pintype "passive"))
    )
    (net (code "46") (name "unconnected-(JA-Pad5)") (class "Default")
      (node (ref "JA") (pin "5") (pinfunction "5_5") (pintype "passive"))
    )
    (net (code "47") (name "unconnected-(JA-Pad6)") (class "Default")
      (node (ref "JA") (pin "6") (pinfunction "6_6") (pintype "passive"))
    )
    (net (code "48") (name "unconnected-(JA-Pad9)") (class "Default")
      (node (ref "JA") (pin "9") (pinfunction "9_9") (pintype "passive"))
    )
    (net (code "49") (name "unconnected-(JA-Pad10)") (class "Default")
      (node (ref "JA") (pin "10") (pinfunction "10_10") (pintype "passive"))
    )
    (net (code "50") (name "unconnected-(JA-Pad11)") (class "Default")
      (node (ref "JA") (pin "11") (pinfunction "11_11") (pintype "passive"))
    )
    (net (code "51") (name "unconnected-(JA-Pad12)") (class "Default")
      (node (ref "JA") (pin "12") (pinfunction "12_12") (pintype "passive"))
    )
    (net (code "52") (name "unconnected-(JA-Pad14)") (class "Default")
      (node (ref "JA") (pin "14") (pinfunction "14_14") (pintype "passive"))
    )
    (net (code "53") (name "unconnected-(JA-Pad15)") (class "Default")
      (node (ref "JA") (pin "15") (pinfunction "15_15") (pintype "passive"))
    )
    (net (code "54") (name "unconnected-(JA-Pad16)") (class "Default")
      (node (ref "JA") (pin "16") (pinfunction "16_16") (pintype "passive"))
    )
    (net (code "55") (name "unconnected-(JA-Pad17)") (class "Default")
      (node (ref "JA") (pin "17") (pinfunction "17_17") (pintype "passive"))
    )
    (net (code "56") (name "unconnected-(JA-Pad18)") (class "Default")
      (node (ref "JA") (pin "18") (pinfunction "18_18") (pintype "passive"))
    )
    (net (code "57") (name "unconnected-(JA-Pad19)") (class "Default")
      (node (ref "JA") (pin "19") (pinfunction "19_19") (pintype "passive"))
    )
    (net (code "58") (name "unconnected-(JA-Pad20)") (class "Default")
      (node (ref "JA") (pin "20") (pinfunction "20_20") (pintype "passive"))
    )
    (net (code "59") (name "unconnected-(JA-Pad24)") (class "Default")
      (node (ref "JA") (pin "24") (pinfunction "24_24") (pintype "passive"))
    )
    (net (code "60") (name "unconnected-(JA-Pad28)") (class "Default")
      (node (ref "JA") (pin "28") (pinfunction "28_28") (pintype "passive"))
    )
    (net (code "61") (name "unconnected-(JA-Pad30)") (class "Default")
      (node (ref "JA") (pin "30") (pinfunction "30_30") (pintype "passive"))
    )
    (net (code "62") (name "unconnected-(JA-Pad31)") (class "Default")
      (node (ref "JA") (pin "31") (pinfunction "31_31") (pintype "passive"))
    )
    (net (code "63") (name "unconnected-(JA-Pad35)") (class "Default")
      (node (ref "JA") (pin "35") (pinfunction "35_35") (pintype "passive"))
    )
    (net (code "64") (name "unconnected-(JA-Pad36)") (class "Default")
      (node (ref "JA") (pin "36") (pinfunction "36_36") (pintype "passive"))
    )
    (net (code "65") (name "unconnected-(JA-Pad37)") (class "Default")
      (node (ref "JA") (pin "37") (pinfunction "37_37") (pintype "passive"))
    )
    (net (code "66") (name "unconnected-(JA-Pad39)") (class "Default")
      (node (ref "JA") (pin "39") (pinfunction "39_39") (pintype "passive"))
    )
    (net (code "67") (name "unconnected-(JA-Pad40)") (class "Default")
      (node (ref "JA") (pin "40") (pinfunction "40_40") (pintype "passive"))
    )
    (net (code "68") (name "unconnected-(JA-Pad41)") (class "Default")
      (node (ref "JA") (pin "41") (pinfunction "41_41") (pintype "passive"))
    )
    (net (code "69") (name "unconnected-(JA-Pad45)") (class "Default")
      (node (ref "JA") (pin "45") (pinfunction "45_45") (pintype "passive"))
    )
    (net (code "70") (name "unconnected-(JA-Pad47)") (class "Default")
      (node (ref "JA") (pin "47") (pinfunction "47_47") (pintype "passive"))
    )
    (net (code "71") (name "unconnected-(JA-Pad48)") (class "Default")
      (node (ref "JA") (pin "48") (pinfunction "48_48") (pintype "passive"))
    )
    (net (code "72") (name "unconnected-(JA-Pad50)") (class "Default")
      (node (ref "JA") (pin "50") (pinfunction "50_50") (pintype "passive"))
    )
    (net (code "73") (name "unconnected-(JA-Pad57)") (class "Default")
      (node (ref "JA") (pin "57") (pinfunction "57_57") (pintype "passive"))
    )
    (net (code "74") (name "unconnected-(JA-Pad61)") (class "Default")
      (node (ref "JA") (pin "61") (pinfunction "61_61") (pintype "passive"))
    )
    (net (code "75") (name "unconnected-(JA-Pad62)") (class "Default")
      (node (ref "JA") (pin "62") (pinfunction "62_62") (pintype "passive"))
    )
    (net (code "76") (name "unconnected-(JA-Pad63)") (class "Default")
      (node (ref "JA") (pin "63") (pinfunction "63_63") (pintype "passive"))
    )
    (net (code "77") (name "unconnected-(JA-Pad64)") (class "Default")
      (node (ref "JA") (pin "64") (pinfunction "64_64") (pintype "passive"))
    )
    (net (code "78") (name "unconnected-(JA-Pad67)") (class "Default")
      (node (ref "JA") (pin "67") (pinfunction "67_67") (pintype "passive"))
    )
    (net (code "79") (name "unconnected-(JA-Pad68)") (class "Default")
      (node (ref "JA") (pin "68") (pinfunction "68_68") (pintype "passive"))
    )
    (net (code "80") (name "unconnected-(JA-Pad69)") (class "Default")
      (node (ref "JA") (pin "69") (pinfunction "69_69") (pintype "passive"))
    )
    (net (code "81") (name "unconnected-(JA-Pad70)") (class "Default")
      (node (ref "JA") (pin "70") (pinfunction "70_70") (pintype "passive"))
    )
    (net (code "82") (name "unconnected-(JA-Pad72)") (class "Default")
      (node (ref "JA") (pin "72") (pinfunction "72_72") (pintype "passive"))
    )
    (net (code "83") (name "unconnected-(JA-Pad73)") (class "Default")
      (node (ref "JA") (pin "73") (pinfunction "73_73") (pintype "passive"))
    )
    (net (code "84") (name "unconnected-(JA-Pad75)") (class "Default")
      (node (ref "JA") (pin "75") (pinfunction "75_75") (pintype "passive"))
    )
    (net (code "85") (name "unconnected-(JA-Pad76)") (class "Default")
      (node (ref "JA") (pin "76") (pinfunction "76_76") (pintype "passive"))
    )
    (net (code "86") (name "unconnected-(JA-Pad78)") (class "Default")
      (node (ref "JA") (pin "78") (pinfunction "78_78") (pintype "passive"))
    )
    (net (code "87") (name "unconnected-(JA-Pad88)") (class "Default")
      (node (ref "JA") (pin "88") (pinfunction "88_88") (pintype "passive"))
    )
    (net (code "88") (name "unconnected-(JA-Pad89)") (class "Default")
      (node (ref "JA") (pin "89") (pinfunction "89_89") (pintype "passive"))
    )
    (net (code "89") (name "unconnected-(JA-Pad90)") (class "Default")
      (node (ref "JA") (pin "90") (pinfunction "90_90") (pintype "passive"))
    )
    (net (code "90") (name "unconnected-(JA-Pad91)") (class "Default")
      (node (ref "JA") (pin "91") (pinfunction "91_91") (pintype "passive"))
    )
    (net (code "91") (name "unconnected-(JA-Pad92)") (class "Default")
      (node (ref "JA") (pin "92") (pinfunction "92_92") (pintype "passive"))
    )
    (net (code "92") (name "unconnected-(JA-Pad93)") (class "Default")
      (node (ref "JA") (pin "93") (pinfunction "93_93") (pintype "passive"))
    )
    (net (code "93") (name "unconnected-(JA-Pad94)") (class "Default")
      (node (ref "JA") (pin "94") (pinfunction "94_94") (pintype "passive"))
    )
    (net (code "94") (name "unconnected-(JA-Pad96)") (class "Default")
      (node (ref "JA") (pin "96") (pinfunction "96_96") (pintype "passive"))
    )
    (net (code "95") (name "unconnected-(JA-Pad97)") (class "Default")
      (node (ref "JA") (pin "97") (pinfunction "97_97") (pintype "passive"))
    )
    (net (code "96") (name "unconnected-(JA-Pad99)") (class "Default")
      (node (ref "JA") (pin "99") (pinfunction "99_99") (pintype "passive"))
    )
    (net (code "97") (name "unconnected-(JA-Pad100)") (class "Default")
      (node (ref "JA") (pin "100") (pinfunction "100_100") (pintype "passive"))
    )
    (net (code "98") (name "unconnected-(JB-Pad1)") (class "Default")
      (node (ref "JB") (pin "1") (pinfunction "1_1") (pintype "passive"))
    )
    (net (code "99") (name "unconnected-(JB-Pad2)") (class "Default")
      (node (ref "JB") (pin "2") (pinfunction "2_2") (pintype "passive"))
    )
    (net (code "100") (name "unconnected-(JB-Pad4)") (class "Default")
      (node (ref "JB") (pin "4") (pinfunction "4_4") (pintype "passive"))
    )
    (net (code "101") (name "unconnected-(JB-Pad6)") (class "Default")
      (node (ref "JB") (pin "6") (pinfunction "6_6") (pintype "passive"))
    )
    (net (code "102") (name "unconnected-(JB-Pad9)") (class "Default")
      (node (ref "JB") (pin "9") (pinfunction "9_9") (pintype "passive"))
    )
    (net (code "103") (name "unconnected-(JB-Pad10)") (class "Default")
      (node (ref "JB") (pin "10") (pinfunction "10_10") (pintype "passive"))
    )
    (net (code "104") (name "unconnected-(JB-Pad11)") (class "Default")
      (node (ref "JB") (pin "11") (pinfunction "11_11") (pintype "passive"))
    )
    (net (code "105") (name "unconnected-(JB-Pad12)") (class "Default")
      (node (ref "JB") (pin "12") (pinfunction "12_12") (pintype "passive"))
    )
    (net (code "106") (name "unconnected-(JB-Pad15)") (class "Default")
      (node (ref "JB") (pin "15") (pinfunction "15_15") (pintype "passive"))
    )
    (net (code "107") (name "unconnected-(JB-Pad16)") (class "Default")
      (node (ref "JB") (pin "16") (pinfunction "16_16") (pintype "passive"))
    )
    (net (code "108") (name "unconnected-(JB-Pad17)") (class "Default")
      (node (ref "JB") (pin "17") (pinfunction "17_17") (pintype "passive"))
    )
    (net (code "109") (name "unconnected-(JB-Pad18)") (class "Default")
      (node (ref "JB") (pin "18") (pinfunction "18_18") (pintype "passive"))
    )
    (net (code "110") (name "unconnected-(JB-Pad21)") (class "Default")
      (node (ref "JB") (pin "21") (pinfunction "21_21") (pintype "passive"))
    )
    (net (code "111") (name "unconnected-(JB-Pad22)") (class "Default")
      (node (ref "JB") (pin "22") (pinfunction "22_22") (pintype "passive"))
    )
    (net (code "112") (name "unconnected-(JB-Pad23)") (class "Default")
      (node (ref "JB") (pin "23") (pinfunction "23_23") (pintype "passive"))
    )
    (net (code "113") (name "unconnected-(JB-Pad24)") (class "Default")
      (node (ref "JB") (pin "24") (pinfunction "24_24") (pintype "passive"))
    )
    (net (code "114") (name "unconnected-(JB-Pad27)") (class "Default")
      (node (ref "JB") (pin "27") (pinfunction "27_27") (pintype "passive"))
    )
    (net (code "115") (name "unconnected-(JB-Pad28)") (class "Default")
      (node (ref "JB") (pin "28") (pinfunction "28_28") (pintype "passive"))
    )
    (net (code "116") (name "unconnected-(JB-Pad29)") (class "Default")
      (node (ref "JB") (pin "29") (pinfunction "29_29") (pintype "passive"))
    )
    (net (code "117") (name "unconnected-(JB-Pad30)") (class "Default")
      (node (ref "JB") (pin "30") (pinfunction "30_30") (pintype "passive"))
    )
    (net (code "118") (name "unconnected-(JB-Pad33)") (class "Default")
      (node (ref "JB") (pin "33") (pinfunction "33_33") (pintype "passive"))
    )
    (net (code "119") (name "unconnected-(JB-Pad34)") (class "Default")
      (node (ref "JB") (pin "34") (pinfunction "34_34") (pintype "passive"))
    )
    (net (code "120") (name "unconnected-(JB-Pad35)") (class "Default")
      (node (ref "JB") (pin "35") (pinfunction "35_35") (pintype "passive"))
    )
    (net (code "121") (name "unconnected-(JB-Pad36)") (class "Default")
      (node (ref "JB") (pin "36") (pinfunction "36_36") (pintype "passive"))
    )
    (net (code "122") (name "unconnected-(JB-Pad39)") (class "Default")
      (node (ref "JB") (pin "39") (pinfunction "39_39") (pintype "passive"))
    )
    (net (code "123") (name "unconnected-(JB-Pad40)") (class "Default")
      (node (ref "JB") (pin "40") (pinfunction "40_40") (pintype "passive"))
    )
    (net (code "124") (name "unconnected-(JB-Pad41)") (class "Default")
      (node (ref "JB") (pin "41") (pinfunction "41_41") (pintype "passive"))
    )
    (net (code "125") (name "unconnected-(JB-Pad42)") (class "Default")
      (node (ref "JB") (pin "42") (pinfunction "42_42") (pintype "passive"))
    )
    (net (code "126") (name "unconnected-(JB-Pad43)") (class "Default")
      (node (ref "JB") (pin "43") (pinfunction "43_43") (pintype "passive"))
    )
    (net (code "127") (name "unconnected-(JB-Pad45)") (class "Default")
      (node (ref "JB") (pin "45") (pinfunction "45_45") (pintype "passive"))
    )
    (net (code "128") (name "unconnected-(JB-Pad46)") (class "Default")
      (node (ref "JB") (pin "46") (pinfunction "46_46") (pintype "passive"))
    )
    (net (code "129") (name "unconnected-(JB-Pad47)") (class "Default")
      (node (ref "JB") (pin "47") (pinfunction "47_47") (pintype "passive"))
    )
    (net (code "130") (name "unconnected-(JB-Pad48)") (class "Default")
      (node (ref "JB") (pin "48") (pinfunction "48_48") (pintype "passive"))
    )
    (net (code "131") (name "unconnected-(JB-Pad49)") (class "Default")
      (node (ref "JB") (pin "49") (pinfunction "49_49") (pintype "passive"))
    )
    (net (code "132") (name "unconnected-(JB-Pad51)") (class "Default")
      (node (ref "JB") (pin "51") (pinfunction "51_51") (pintype "passive"))
    )
    (net (code "133") (name "unconnected-(JB-Pad52)") (class "Default")
      (node (ref "JB") (pin "52") (pinfunction "52_52") (pintype "passive"))
    )
    (net (code "134") (name "unconnected-(JB-Pad53)") (class "Default")
      (node (ref "JB") (pin "53") (pinfunction "53_53") (pintype "passive"))
    )
    (net (code "135") (name "unconnected-(JB-Pad54)") (class "Default")
      (node (ref "JB") (pin "54") (pinfunction "54_54") (pintype "passive"))
    )
    (net (code "136") (name "unconnected-(JB-Pad57)") (class "Default")
      (node (ref "JB") (pin "57") (pinfunction "57_57") (pintype "passive"))
    )
    (net (code "137") (name "unconnected-(JB-Pad58)") (class "Default")
      (node (ref "JB") (pin "58") (pinfunction "58_58") (pintype "passive"))
    )
    (net (code "138") (name "unconnected-(JB-Pad59)") (class "Default")
      (node (ref "JB") (pin "59") (pinfunction "59_59") (pintype "passive"))
    )
    (net (code "139") (name "unconnected-(JB-Pad60)") (class "Default")
      (node (ref "JB") (pin "60") (pinfunction "60_60") (pintype "passive"))
    )
    (net (code "140") (name "unconnected-(JB-Pad63)") (class "Default")
      (node (ref "JB") (pin "63") (pinfunction "63_63") (pintype "passive"))
    )
    (net (code "141") (name "unconnected-(JB-Pad64)") (class "Default")
      (node (ref "JB") (pin "64") (pinfunction "64_64") (pintype "passive"))
    )
    (net (code "142") (name "unconnected-(JB-Pad65)") (class "Default")
      (node (ref "JB") (pin "65") (pinfunction "65_65") (pintype "passive"))
    )
    (net (code "143") (name "unconnected-(JB-Pad66)") (class "Default")
      (node (ref "JB") (pin "66") (pinfunction "66_66") (pintype "passive"))
    )
    (net (code "144") (name "unconnected-(JB-Pad69)") (class "Default")
      (node (ref "JB") (pin "69") (pinfunction "69_69") (pintype "passive"))
    )
    (net (code "145") (name "unconnected-(JB-Pad70)") (class "Default")
      (node (ref "JB") (pin "70") (pinfunction "70_70") (pintype "passive"))
    )
    (net (code "146") (name "unconnected-(JB-Pad71)") (class "Default")
      (node (ref "JB") (pin "71") (pinfunction "71_71") (pintype "passive"))
    )
    (net (code "147") (name "unconnected-(JB-Pad72)") (class "Default")
      (node (ref "JB") (pin "72") (pinfunction "72_72") (pintype "passive"))
    )
    (net (code "148") (name "unconnected-(JB-Pad75)") (class "Default")
      (node (ref "JB") (pin "75") (pinfunction "75_75") (pintype "passive"))
    )
    (net (code "149") (name "unconnected-(JB-Pad76)") (class "Default")
      (node (ref "JB") (pin "76") (pinfunction "76_76") (pintype "passive"))
    )
    (net (code "150") (name "unconnected-(JB-Pad77)") (class "Default")
      (node (ref "JB") (pin "77") (pinfunction "77_77") (pintype "passive"))
    )
    (net (code "151") (name "unconnected-(JB-Pad78)") (class "Default")
      (node (ref "JB") (pin "78") (pinfunction "78_78") (pintype "passive"))
    )
    (net (code "152") (name "unconnected-(JB-Pad81)") (class "Default")
      (node (ref "JB") (pin "81") (pinfunction "81_81") (pintype "passive"))
    )
    (net (code "153") (name "unconnected-(JB-Pad82)") (class "Default")
      (node (ref "JB") (pin "82") (pinfunction "82_82") (pintype "passive"))
    )
    (net (code "154") (name "unconnected-(JB-Pad83)") (class "Default")
      (node (ref "JB") (pin "83") (pinfunction "83_83") (pintype "passive"))
    )
    (net (code "155") (name "unconnected-(JB-Pad84)") (class "Default")
      (node (ref "JB") (pin "84") (pinfunction "84_84") (pintype "passive"))
    )
    (net (code "156") (name "unconnected-(JB-Pad87)") (class "Default")
      (node (ref "JB") (pin "87") (pinfunction "87_87") (pintype "passive"))
    )
    (net (code "157") (name "unconnected-(JB-Pad88)") (class "Default")
      (node (ref "JB") (pin "88") (pinfunction "88_88") (pintype "passive"))
    )
    (net (code "158") (name "unconnected-(JB-Pad89)") (class "Default")
      (node (ref "JB") (pin "89") (pinfunction "89_89") (pintype "passive"))
    )
    (net (code "159") (name "unconnected-(JB-Pad90)") (class "Default")
      (node (ref "JB") (pin "90") (pinfunction "90_90") (pintype "passive"))
    )
    (net (code "160") (name "unconnected-(JB-Pad93)") (class "Default")
      (node (ref "JB") (pin "93") (pinfunction "93_93") (pintype "passive"))
    )
    (net (code "161") (name "unconnected-(JB-Pad94)") (class "Default")
      (node (ref "JB") (pin "94") (pinfunction "94_94") (pintype "passive"))
    )
    (net (code "162") (name "unconnected-(JB-Pad95)") (class "Default")
      (node (ref "JB") (pin "95") (pinfunction "95_95") (pintype "passive"))
    )
    (net (code "163") (name "unconnected-(JB-Pad96)") (class "Default")
      (node (ref "JB") (pin "96") (pinfunction "96_96") (pintype "passive"))
    )
    (net (code "164") (name "unconnected-(JB-Pad99)") (class "Default")
      (node (ref "JB") (pin "99") (pinfunction "99_99") (pintype "passive"))
    )
    (net (code "165") (name "unconnected-(JB-Pad100)") (class "Default")
      (node (ref "JB") (pin "100") (pinfunction "100_100") (pintype "passive"))
    )
    (net (code "166") (name "unconnected-(U1-PadA1)") (class "Default")
      (node (ref "U1") (pin "A1") (pinfunction "A1_A1") (pintype "bidirectional"))
    )
    (net (code "167") (name "unconnected-(U1-PadA2)") (class "Default")
      (node (ref "U1") (pin "A2") (pinfunction "A2_A2") (pintype "bidirectional"))
    )
    (net (code "168") (name "unconnected-(U1-PadA7)") (class "Default")
      (node (ref "U1") (pin "A7") (pinfunction "A7_A7") (pintype "bidirectional"))
    )
    (net (code "169") (name "unconnected-(U1-PadA8)") (class "Default")
      (node (ref "U1") (pin "A8") (pinfunction "A8_A8") (pintype "bidirectional"))
    )
    (net (code "170") (name "unconnected-(U1-PadA9)") (class "Default")
      (node (ref "U1") (pin "A9") (pinfunction "A9_A9") (pintype "bidirectional"))
    )
    (net (code "171") (name "unconnected-(U1-PadA10)") (class "Default")
      (node (ref "U1") (pin "A10") (pinfunction "A10_A10") (pintype "bidirectional"))
    )
    (net (code "172") (name "unconnected-(U1-PadA11)") (class "Default")
      (node (ref "U1") (pin "A11") (pinfunction "A11_A11") (pintype "bidirectional"))
    )
    (net (code "173") (name "unconnected-(U1-PadA12)") (class "Default")
      (node (ref "U1") (pin "A12") (pinfunction "A12_A12") (pintype "bidirectional"))
    )
    (net (code "174") (name "unconnected-(U1-PadA13)") (class "Default")
      (node (ref "U1") (pin "A13") (pinfunction "A13_A13") (pintype "bidirectional"))
    )
    (net (code "175") (name "unconnected-(U1-PadA14)") (class "Default")
      (node (ref "U1") (pin "A14") (pinfunction "A14_A14") (pintype "bidirectional"))
    )
    (net (code "176") (name "unconnected-(U1-PadB1)") (class "Default")
      (node (ref "U1") (pin "B1") (pinfunction "B1_B1") (pintype "bidirectional"))
    )
    (net (code "177") (name "unconnected-(U1-PadB7)") (class "Default")
      (node (ref "U1") (pin "B7") (pinfunction "B7_B7") (pintype "bidirectional"))
    )
    (net (code "178") (name "unconnected-(U1-PadB8)") (class "Default")
      (node (ref "U1") (pin "B8") (pinfunction "B8_B8") (pintype "bidirectional"))
    )
    (net (code "179") (name "unconnected-(U1-PadB9)") (class "Default")
      (node (ref "U1") (pin "B9") (pinfunction "B9_B9") (pintype "bidirectional"))
    )
    (net (code "180") (name "unconnected-(U1-PadB10)") (class "Default")
      (node (ref "U1") (pin "B10") (pinfunction "B10_B10") (pintype "bidirectional"))
    )
    (net (code "181") (name "unconnected-(U1-PadB11)") (class "Default")
      (node (ref "U1") (pin "B11") (pinfunction "B11_B11") (pintype "bidirectional"))
    )
    (net (code "182") (name "unconnected-(U1-PadB12)") (class "Default")
      (node (ref "U1") (pin "B12") (pinfunction "B12_B12") (pintype "bidirectional"))
    )
    (net (code "183") (name "unconnected-(U1-PadB13)") (class "Default")
      (node (ref "U1") (pin "B13") (pinfunction "B13_B13") (pintype "bidirectional"))
    )
    (net (code "184") (name "unconnected-(U1-PadB14)") (class "Default")
      (node (ref "U1") (pin "B14") (pinfunction "B14_B14") (pintype "bidirectional"))
    )
    (net (code "185") (name "unconnected-(U1-PadC1)") (class "Default")
      (node (ref "U1") (pin "C1") (pinfunction "C1_C1") (pintype "bidirectional"))
    )
    (net (code "186") (name "unconnected-(U1-PadC3)") (class "Default")
      (node (ref "U1") (pin "C3") (pinfunction "C3_C3") (pintype "bidirectional"))
    )
    (net (code "187") (name "unconnected-(U1-PadC5)") (class "Default")
      (node (ref "U1") (pin "C5") (pinfunction "C5_C5") (pintype "bidirectional"))
    )
    (net (code "188") (name "unconnected-(U1-PadC7)") (class "Default")
      (node (ref "U1") (pin "C7") (pinfunction "C7_C7") (pintype "bidirectional"))
    )
    (net (code "189") (name "unconnected-(U1-PadC8)") (class "Default")
      (node (ref "U1") (pin "C8") (pinfunction "C8_C8") (pintype "bidirectional"))
    )
    (net (code "190") (name "unconnected-(U1-PadC9)") (class "Default")
      (node (ref "U1") (pin "C9") (pinfunction "C9_C9") (pintype "bidirectional"))
    )
    (net (code "191") (name "unconnected-(U1-PadC10)") (class "Default")
      (node (ref "U1") (pin "C10") (pinfunction "C10_C10") (pintype "bidirectional"))
    )
    (net (code "192") (name "unconnected-(U1-PadC11)") (class "Default")
      (node (ref "U1") (pin "C11") (pinfunction "C11_C11") (pintype "bidirectional"))
    )
    (net (code "193") (name "unconnected-(U1-PadC12)") (class "Default")
      (node (ref "U1") (pin "C12") (pinfunction "C12_C12") (pintype "bidirectional"))
    )
    (net (code "194") (name "unconnected-(U1-PadC13)") (class "Default")
      (node (ref "U1") (pin "C13") (pinfunction "C13_C13") (pintype "bidirectional"))
    )
    (net (code "195") (name "unconnected-(U1-PadC14)") (class "Default")
      (node (ref "U1") (pin "C14") (pinfunction "C14_C14") (pintype "bidirectional"))
    )
    (net (code "196") (name "unconnected-(U1-PadD1)") (class "Default")
      (node (ref "U1") (pin "D1") (pinfunction "D1_D1") (pintype "bidirectional"))
    )
    (net (code "197") (name "unconnected-(U1-PadD2)") (class "Default")
      (node (ref "U1") (pin "D2") (pinfunction "D2_D2") (pintype "bidirectional"))
    )
    (net (code "198") (name "unconnected-(U1-PadD3)") (class "Default")
      (node (ref "U1") (pin "D3") (pinfunction "D3_D3") (pintype "bidirectional"))
    )
    (net (code "199") (name "unconnected-(U1-PadD4)") (class "Default")
      (node (ref "U1") (pin "D4") (pinfunction "D4_D4") (pintype "bidirectional"))
    )
    (net (code "200") (name "unconnected-(U1-PadD12)") (class "Default")
      (node (ref "U1") (pin "D12") (pinfunction "D12_D12") (pintype "bidirectional"))
    )
    (net (code "201") (name "unconnected-(U1-PadD13)") (class "Default")
      (node (ref "U1") (pin "D13") (pinfunction "D13_D13") (pintype "bidirectional"))
    )
    (net (code "202") (name "unconnected-(U1-PadD14)") (class "Default")
      (node (ref "U1") (pin "D14") (pinfunction "D14_D14") (pintype "bidirectional"))
    )
    (net (code "203") (name "unconnected-(U1-PadE1)") (class "Default")
      (node (ref "U1") (pin "E1") (pinfunction "E1_E1") (pintype "bidirectional"))
    )
    (net (code "204") (name "unconnected-(U1-PadE2)") (class "Default")
      (node (ref "U1") (pin "E2") (pinfunction "E2_E2") (pintype "bidirectional"))
    )
    (net (code "205") (name "unconnected-(U1-PadE3)") (class "Default")
      (node (ref "U1") (pin "E3") (pinfunction "E3_E3") (pintype "bidirectional"))
    )
    (net (code "206") (name "unconnected-(U1-PadE5)") (class "Default")
      (node (ref "U1") (pin "E5") (pinfunction "E5_E5") (pintype "bidirectional"))
    )
    (net (code "207") (name "unconnected-(U1-PadE8)") (class "Default")
      (node (ref "U1") (pin "E8") (pinfunction "E8_E8") (pintype "bidirectional"))
    )
    (net (code "208") (name "unconnected-(U1-PadE9)") (class "Default")
      (node (ref "U1") (pin "E9") (pinfunction "E9_E9") (pintype "bidirectional"))
    )
    (net (code "209") (name "unconnected-(U1-PadE10)") (class "Default")
      (node (ref "U1") (pin "E10") (pinfunction "E10_E10") (pintype "bidirectional"))
    )
    (net (code "210") (name "unconnected-(U1-PadE12)") (class "Default")
      (node (ref "U1") (pin "E12") (pinfunction "E12_E12") (pintype "bidirectional"))
    )
    (net (code "211") (name "unconnected-(U1-PadE13)") (class "Default")
      (node (ref "U1") (pin "E13") (pinfunction "E13_E13") (pintype "bidirectional"))
    )
    (net (code "212") (name "unconnected-(U1-PadE14)") (class "Default")
      (node (ref "U1") (pin "E14") (pinfunction "E14_E14") (pintype "bidirectional"))
    )
    (net (code "213") (name "unconnected-(U1-PadF1)") (class "Default")
      (node (ref "U1") (pin "F1") (pinfunction "F1_F1") (pintype "bidirectional"))
    )
    (net (code "214") (name "unconnected-(U1-PadF2)") (class "Default")
      (node (ref "U1") (pin "F2") (pinfunction "F2_F2") (pintype "bidirectional"))
    )
    (net (code "215") (name "unconnected-(U1-PadF3)") (class "Default")
      (node (ref "U1") (pin "F3") (pinfunction "F3_F3") (pintype "bidirectional"))
    )
    (net (code "216") (name "unconnected-(U1-PadF10)") (class "Default")
      (node (ref "U1") (pin "F10") (pinfunction "F10_F10") (pintype "bidirectional"))
    )
    (net (code "217") (name "unconnected-(U1-PadF12)") (class "Default")
      (node (ref "U1") (pin "F12") (pinfunction "F12_F12") (pintype "bidirectional"))
    )
    (net (code "218") (name "unconnected-(U1-PadF13)") (class "Default")
      (node (ref "U1") (pin "F13") (pinfunction "F13_F13") (pintype "bidirectional"))
    )
    (net (code "219") (name "unconnected-(U1-PadF14)") (class "Default")
      (node (ref "U1") (pin "F14") (pinfunction "F14_F14") (pintype "bidirectional"))
    )
    (net (code "220") (name "unconnected-(U1-PadG1)") (class "Default")
      (node (ref "U1") (pin "G1") (pinfunction "G1_G1") (pintype "bidirectional"))
    )
    (net (code "221") (name "unconnected-(U1-PadG2)") (class "Default")
      (node (ref "U1") (pin "G2") (pinfunction "G2_G2") (pintype "bidirectional"))
    )
    (net (code "222") (name "unconnected-(U1-PadG3)") (class "Default")
      (node (ref "U1") (pin "G3") (pinfunction "G3_G3") (pintype "bidirectional"))
    )
    (net (code "223") (name "unconnected-(U1-PadG10)") (class "Default")
      (node (ref "U1") (pin "G10") (pinfunction "G10_G10") (pintype "bidirectional"))
    )
    (net (code "224") (name "unconnected-(U1-PadG12)") (class "Default")
      (node (ref "U1") (pin "G12") (pinfunction "G12_G12") (pintype "bidirectional"))
    )
    (net (code "225") (name "unconnected-(U1-PadG13)") (class "Default")
      (node (ref "U1") (pin "G13") (pinfunction "G13_G13") (pintype "bidirectional"))
    )
    (net (code "226") (name "unconnected-(U1-PadG14)") (class "Default")
      (node (ref "U1") (pin "G14") (pinfunction "G14_G14") (pintype "bidirectional"))
    )
    (net (code "227") (name "unconnected-(U1-PadH1)") (class "Default")
      (node (ref "U1") (pin "H1") (pinfunction "H1_H1") (pintype "bidirectional"))
    )
    (net (code "228") (name "unconnected-(U1-PadH2)") (class "Default")
      (node (ref "U1") (pin "H2") (pinfunction "H2_H2") (pintype "bidirectional"))
    )
    (net (code "229") (name "unconnected-(U1-PadH3)") (class "Default")
      (node (ref "U1") (pin "H3") (pinfunction "H3_H3") (pintype "bidirectional"))
    )
    (net (code "230") (name "unconnected-(U1-PadH12)") (class "Default")
      (node (ref "U1") (pin "H12") (pinfunction "H12_H12") (pintype "bidirectional"))
    )
    (net (code "231") (name "unconnected-(U1-PadH13)") (class "Default")
      (node (ref "U1") (pin "H13") (pinfunction "H13_H13") (pintype "bidirectional"))
    )
    (net (code "232") (name "unconnected-(U1-PadH14)") (class "Default")
      (node (ref "U1") (pin "H14") (pinfunction "H14_H14") (pintype "bidirectional"))
    )
    (net (code "233") (name "unconnected-(U1-PadJ1)") (class "Default")
      (node (ref "U1") (pin "J1") (pinfunction "J1_J1") (pintype "bidirectional"))
    )
    (net (code "234") (name "unconnected-(U1-PadJ2)") (class "Default")
      (node (ref "U1") (pin "J2") (pinfunction "J2_J2") (pintype "bidirectional"))
    )
    (net (code "235") (name "unconnected-(U1-PadJ3)") (class "Default")
      (node (ref "U1") (pin "J3") (pinfunction "J3_J3") (pintype "bidirectional"))
    )
    (net (code "236") (name "unconnected-(U1-PadJ12)") (class "Default")
      (node (ref "U1") (pin "J12") (pinfunction "J12_J12") (pintype "bidirectional"))
    )
    (net (code "237") (name "unconnected-(U1-PadJ13)") (class "Default")
      (node (ref "U1") (pin "J13") (pinfunction "J13_J13") (pintype "bidirectional"))
    )
    (net (code "238") (name "unconnected-(U1-PadJ14)") (class "Default")
      (node (ref "U1") (pin "J14") (pinfunction "J14_J14") (pintype "bidirectional"))
    )
    (net (code "239") (name "unconnected-(U1-PadK1)") (class "Default")
      (node (ref "U1") (pin "K1") (pinfunction "K1_K1") (pintype "bidirectional"))
    )
    (net (code "240") (name "unconnected-(U1-PadK2)") (class "Default")
      (node (ref "U1") (pin "K2") (pinfunction "K2_K2") (pintype "bidirectional"))
    )
    (net (code "241") (name "unconnected-(U1-PadK3)") (class "Default")
      (node (ref "U1") (pin "K3") (pinfunction "K3_K3") (pintype "bidirectional"))
    )
    (net (code "242") (name "unconnected-(U1-PadK6)") (class "Default")
      (node (ref "U1") (pin "K6") (pinfunction "K6_K6") (pintype "bidirectional"))
    )
    (net (code "243") (name "unconnected-(U1-PadK7)") (class "Default")
      (node (ref "U1") (pin "K7") (pinfunction "K7_K7") (pintype "bidirectional"))
    )
    (net (code "244") (name "unconnected-(U1-PadK10)") (class "Default")
      (node (ref "U1") (pin "K10") (pinfunction "K10_K10") (pintype "bidirectional"))
    )
    (net (code "245") (name "unconnected-(U1-PadK12)") (class "Default")
      (node (ref "U1") (pin "K12") (pinfunction "K12_K12") (pintype "bidirectional"))
    )
    (net (code "246") (name "unconnected-(U1-PadK13)") (class "Default")
      (node (ref "U1") (pin "K13") (pinfunction "K13_K13") (pintype "bidirectional"))
    )
    (net (code "247") (name "unconnected-(U1-PadK14)") (class "Default")
      (node (ref "U1") (pin "K14") (pinfunction "K14_K14") (pintype "bidirectional"))
    )
    (net (code "248") (name "unconnected-(U1-PadL1)") (class "Default")
      (node (ref "U1") (pin "L1") (pinfunction "L1_L1") (pintype "bidirectional"))
    )
    (net (code "249") (name "unconnected-(U1-PadL2)") (class "Default")
      (node (ref "U1") (pin "L2") (pinfunction "L2_L2") (pintype "bidirectional"))
    )
    (net (code "250") (name "unconnected-(U1-PadL3)") (class "Default")
      (node (ref "U1") (pin "L3") (pinfunction "L3_L3") (pintype "bidirectional"))
    )
    (net (code "251") (name "unconnected-(U1-PadL12)") (class "Default")
      (node (ref "U1") (pin "L12") (pinfunction "L12_L12") (pintype "bidirectional"))
    )
    (net (code "252") (name "unconnected-(U1-PadL13)") (class "Default")
      (node (ref "U1") (pin "L13") (pinfunction "L13_L13") (pintype "bidirectional"))
    )
    (net (code "253") (name "unconnected-(U1-PadL14)") (class "Default")
      (node (ref "U1") (pin "L14") (pinfunction "L14_L14") (pintype "bidirectional"))
    )
    (net (code "254") (name "unconnected-(U1-PadM1)") (class "Default")
      (node (ref "U1") (pin "M1") (pinfunction "M1_M1") (pintype "bidirectional"))
    )
    (net (code "255") (name "unconnected-(U1-PadM2)") (class "Default")
      (node (ref "U1") (pin "M2") (pinfunction "M2_M2") (pintype "bidirectional"))
    )
    (net (code "256") (name "unconnected-(U1-PadM3)") (class "Default")
      (node (ref "U1") (pin "M3") (pinfunction "M3_M3") (pintype "bidirectional"))
    )
    (net (code "257") (name "unconnected-(U1-PadM7)") (class "Default")
      (node (ref "U1") (pin "M7") (pinfunction "M7_M7") (pintype "bidirectional"))
    )
    (net (code "258") (name "unconnected-(U1-PadM8)") (class "Default")
      (node (ref "U1") (pin "M8") (pinfunction "M8_M8") (pintype "bidirectional"))
    )
    (net (code "259") (name "unconnected-(U1-PadM9)") (class "Default")
      (node (ref "U1") (pin "M9") (pinfunction "M9_M9") (pintype "bidirectional"))
    )
    (net (code "260") (name "unconnected-(U1-PadM10)") (class "Default")
      (node (ref "U1") (pin "M10") (pinfunction "M10_M10") (pintype "bidirectional"))
    )
    (net (code "261") (name "unconnected-(U1-PadM11)") (class "Default")
      (node (ref "U1") (pin "M11") (pinfunction "M11_M11") (pintype "bidirectional"))
    )
    (net (code "262") (name "unconnected-(U1-PadM12)") (class "Default")
      (node (ref "U1") (pin "M12") (pinfunction "M12_M12") (pintype "bidirectional"))
    )
    (net (code "263") (name "unconnected-(U1-PadM13)") (class "Default")
      (node (ref "U1") (pin "M13") (pinfunction "M13_M13") (pintype "bidirectional"))
    )
    (net (code "264") (name "unconnected-(U1-PadM14)") (class "Default")
      (node (ref "U1") (pin "M14") (pinfunction "M14_M14") (pintype "bidirectional"))
    )
    (net (code "265") (name "unconnected-(U1-PadN1)") (class "Default")
      (node (ref "U1") (pin "N1") (pinfunction "N1_N1") (pintype "bidirectional"))
    )
    (net (code "266") (name "unconnected-(U1-PadN3)") (class "Default")
      (node (ref "U1") (pin "N3") (pinfunction "N3_N3") (pintype "bidirectional"))
    )
    (net (code "267") (name "unconnected-(U1-PadN6)") (class "Default")
      (node (ref "U1") (pin "N6") (pinfunction "N6_N6") (pintype "bidirectional"))
    )
    (net (code "268") (name "unconnected-(U1-PadN7)") (class "Default")
      (node (ref "U1") (pin "N7") (pinfunction "N7_N7") (pintype "bidirectional"))
    )
    (net (code "269") (name "unconnected-(U1-PadN8)") (class "Default")
      (node (ref "U1") (pin "N8") (pinfunction "N8_N8") (pintype "bidirectional"))
    )
    (net (code "270") (name "unconnected-(U1-PadN9)") (class "Default")
      (node (ref "U1") (pin "N9") (pinfunction "N9_N9") (pintype "bidirectional"))
    )
    (net (code "271") (name "unconnected-(U1-PadN10)") (class "Default")
      (node (ref "U1") (pin "N10") (pinfunction "N10_N10") (pintype "bidirectional"))
    )
    (net (code "272") (name "unconnected-(U1-PadN11)") (class "Default")
      (node (ref "U1") (pin "N11") (pinfunction "N11_N11") (pintype "bidirectional"))
    )
    (net (code "273") (name "unconnected-(U1-PadN12)") (class "Default")
      (node (ref "U1") (pin "N12") (pinfunction "N12_N12") (pintype "bidirectional"))
    )
    (net (code "274") (name "unconnected-(U1-PadN13)") (class "Default")
      (node (ref "U1") (pin "N13") (pinfunction "N13_N13") (pintype "bidirectional"))
    )
    (net (code "275") (name "unconnected-(U1-PadN14)") (class "Default")
      (node (ref "U1") (pin "N14") (pinfunction "N14_N14") (pintype "bidirectional"))
    )
    (net (code "276") (name "unconnected-(U1-PadP1)") (class "Default")
      (node (ref "U1") (pin "P1") (pinfunction "P1_P1") (pintype "bidirectional"))
    )
    (net (code "277") (name "unconnected-(U1-PadP2)") (class "Default")
      (node (ref "U1") (pin "P2") (pinfunction "P2_P2") (pintype "bidirectional"))
    )
    (net (code "278") (name "unconnected-(U1-PadP7)") (class "Default")
      (node (ref "U1") (pin "P7") (pinfunction "P7_P7") (pintype "bidirectional"))
    )
    (net (code "279") (name "unconnected-(U1-PadP8)") (class "Default")
      (node (ref "U1") (pin "P8") (pinfunction "P8_P8") (pintype "bidirectional"))
    )
    (net (code "280") (name "unconnected-(U1-PadP9)") (class "Default")
      (node (ref "U1") (pin "P9") (pinfunction "P9_P9") (pintype "bidirectional"))
    )
    (net (code "281") (name "unconnected-(U1-PadP10)") (class "Default")
      (node (ref "U1") (pin "P10") (pinfunction "P10_P10") (pintype "bidirectional"))
    )
    (net (code "282") (name "unconnected-(U1-PadP11)") (class "Default")
      (node (ref "U1") (pin "P11") (pinfunction "P11_P11") (pintype "bidirectional"))
    )
    (net (code "283") (name "unconnected-(U1-PadP12)") (class "Default")
      (node (ref "U1") (pin "P12") (pinfunction "P12_P12") (pintype "bidirectional"))
    )
    (net (code "284") (name "unconnected-(U1-PadP13)") (class "Default")
      (node (ref "U1") (pin "P13") (pinfunction "P13_P13") (pintype "bidirectional"))
    )
    (net (code "285") (name "unconnected-(U1-PadP14)") (class "Default")
      (node (ref "U1") (pin "P14") (pinfunction "P14_P14") (pintype "bidirectional"))
    )
    (net (code "286") (name "unconnected-(U1A-DAT4-PadB3)") (class "Default")
      (node (ref "U1") (pin "B3") (pinfunction "DAT4_B3") (pintype "bidirectional"))
    )
    (net (code "287") (name "unconnected-(U1A-DAT5-PadB4)") (class "Default")
      (node (ref "U1") (pin "B4") (pinfunction "DAT5_B4") (pintype "bidirectional"))
    )
    (net (code "288") (name "unconnected-(U1A-DAT6-PadB5)") (class "Default")
      (node (ref "U1") (pin "B5") (pinfunction "DAT6_B5") (pintype "bidirectional"))
    )
    (net (code "289") (name "unconnected-(U1A-DAT7-PadB6)") (class "Default")
      (node (ref "U1") (pin "B6") (pinfunction "DAT7_B6") (pintype "bidirectional"))
    )
    (net (code "290") (name "unconnected-(U1A-DATA_STROBE-PadH5)") (class "Default")
      (node (ref "U1") (pin "H5") (pinfunction "DATA_STROBE_H5") (pintype "passive"))
    )
    (net (code "291") (name "unconnected-(U1A-RSTN-PadK5)") (class "Default")
      (node (ref "U1") (pin "K5") (pinfunction "RSTN_K5") (pintype "passive"))
    )
    (net (code "292") (name "unconnected-(U2-EN-Pad3)") (class "Default")
      (node (ref "U2") (pin "3") (pinfunction "EN_3") (pintype "input"))
    )
    (net (code "293") (name "unconnected-(U5-IO5-Pad5)") (class "Default")
      (node (ref "U5") (pin "5") (pinfunction "IO5_5") (pintype "bidirectional"))
    )
    (net (code "294") (name "unconnected-(U5-IO8-Pad12)") (class "Default")
      (node (ref "U5") (pin "12") (pinfunction "IO8_12") (pintype "bidirectional"))
    )
    (net (code "295") (name "unconnected-(U5-IO10-Pad18)") (class "Default")
      (node (ref "U5") (pin "18") (pinfunction "IO10_18") (pintype "bidirectional"))
    )
  )
)
